# CP_Scheme.net
KiCad netlist of a schematic drawn in Altium Designer
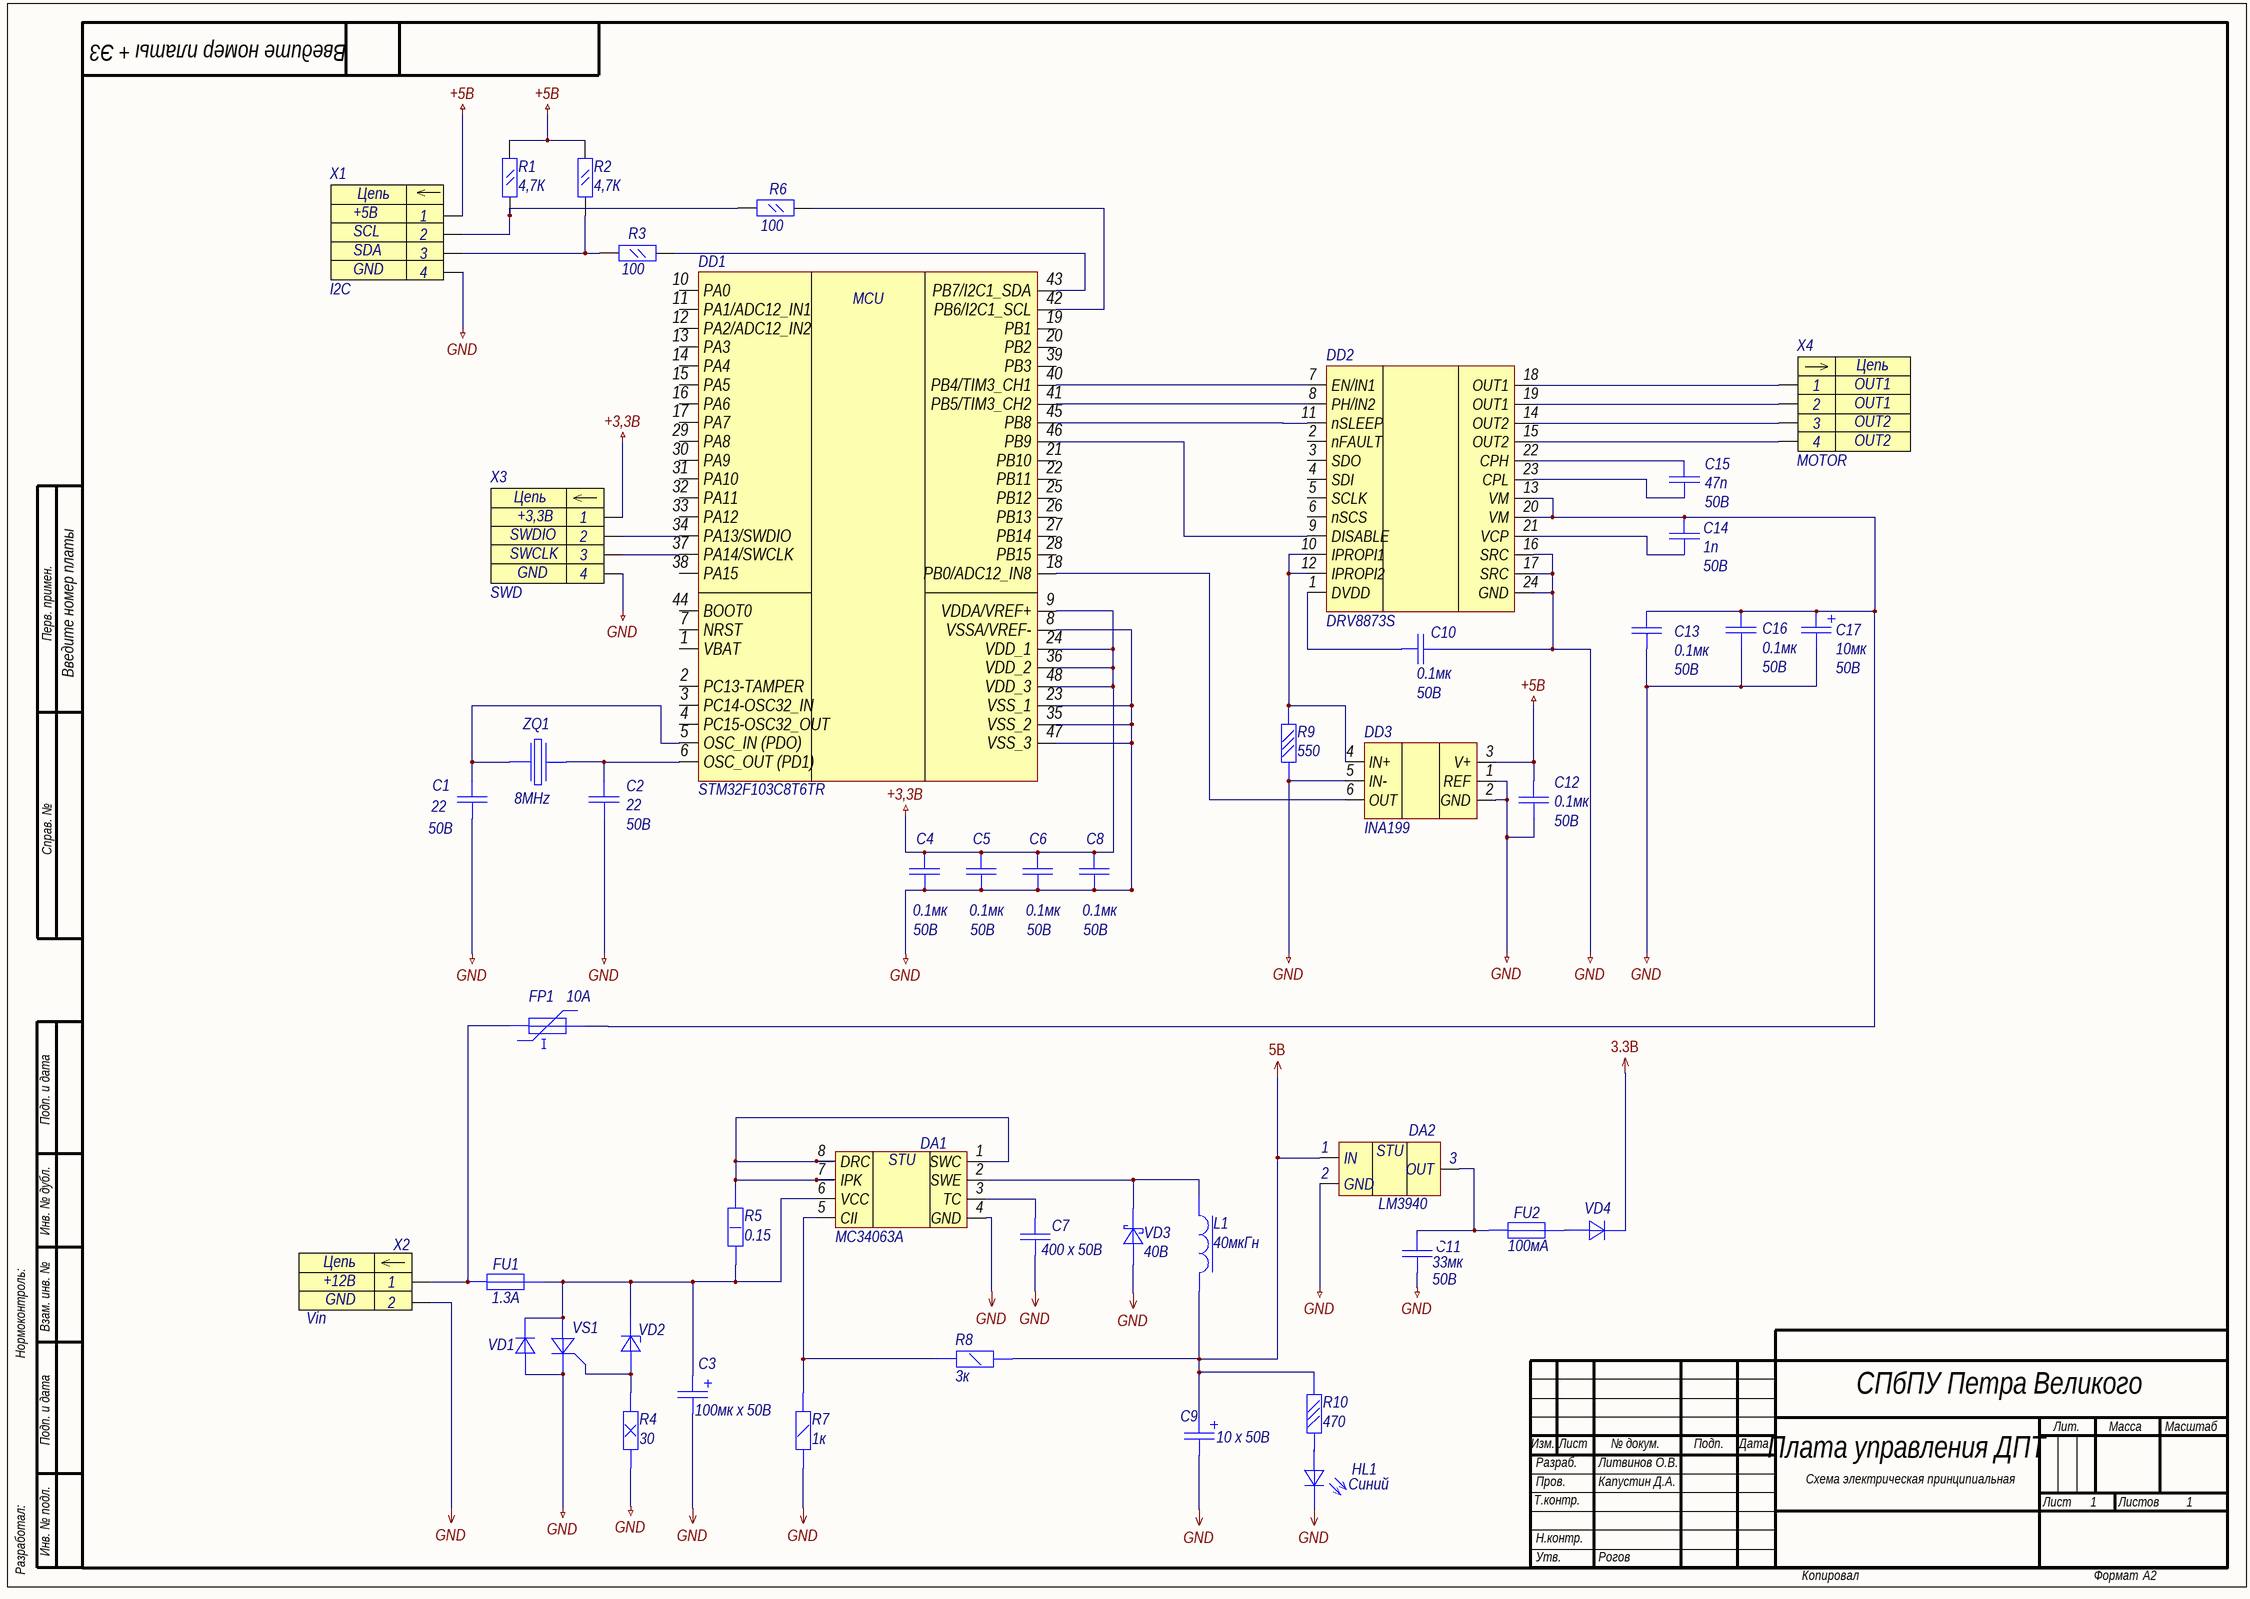
[diagram p0: CP_Scheme.SchDoc]

(export (version "E")
  (design (tool "Eeschema 10.0.6"))
  (components
    (comp (ref "C1")
      (value "22")
      (footprint "C0603")
      (fields (field (name "VOLTAGE") "50В") (field (name "Comment") "Capacitor"))
      (libsource (lib "Capacitor_GOST") (part "Capacitor"))
    )
    (comp (ref "C2")
      (value "22")
      (footprint "C0603")
      (fields (field (name "VOLTAGE") "50В") (field (name "Comment") "Capacitor"))
      (libsource (lib "Capacitor_GOST") (part "Capacitor"))
    )
    (comp (ref "C3")
      (value "Capacitor-E")
      (footprint "C1206")
      (fields (field (name "ЁМКОСТЬ") "100мк х 50В") (field (name "PUBLISHER") "Олег Литвинов"))
      (libsource (lib "Capacitor GOST") (part "Capacitor-E"))
    )
    (comp (ref "C4")
      (value "0.1мк")
      (footprint "C0603")
      (fields (field (name "VOLTAGE") "50В") (field (name "Comment") "Capacitor"))
      (libsource (lib "Capacitor_GOST") (part "Capacitor"))
    )
    (comp (ref "C5")
      (value "0.1мк")
      (footprint "C0603")
      (fields (field (name "VOLTAGE") "50В") (field (name "Comment") "Capacitor"))
      (libsource (lib "Capacitor_GOST") (part "Capacitor"))
    )
    (comp (ref "C6")
      (value "0.1мк")
      (footprint "C0603")
      (fields (field (name "VOLTAGE") "50В") (field (name "Comment") "Capacitor"))
      (libsource (lib "Capacitor_GOST") (part "Capacitor"))
    )
    (comp (ref "C7")
      (value "Capacitor")
      (footprint "R0805")
      (fields (field (name "ЁМКОСТЬ") "400 х 50В") (field (name "PUBLISHER") "Andrew Danich"))
      (libsource (lib "Capacitor GOST") (part "Capacitor"))
    )
    (comp (ref "C8")
      (value "0.1мк")
      (footprint "C0603")
      (fields (field (name "VOLTAGE") "50В") (field (name "Comment") "Capacitor"))
      (libsource (lib "Capacitor_GOST") (part "Capacitor"))
    )
    (comp (ref "C9")
      (value "Capacitor-E")
      (footprint "C1206")
      (fields (field (name "ЁМКОСТЬ") "10 х 50В") (field (name "PUBLISHER") "Олег Литвинов"))
      (libsource (lib "Capacitor GOST") (part "Capacitor-E"))
    )
    (comp (ref "C10")
      (value "0.1мк")
      (footprint "C0603")
      (fields (field (name "VOLTAGE") "50В") (field (name "Comment") "Capacitor"))
      (libsource (lib "Capacitor_GOST") (part "Capacitor"))
    )
    (comp (ref "C11")
      (value "33мк")
      (footprint "C0805")
      (fields (field (name "VOLTAGE") "50В") (field (name "Comment") "Capacitor"))
      (libsource (lib "Capacitor_GOST") (part "Capacitor"))
    )
    (comp (ref "C12")
      (value "0.1мк")
      (footprint "C0603")
      (fields (field (name "VOLTAGE") "50В") (field (name "Comment") "Capacitor"))
      (libsource (lib "Capacitor_GOST") (part "Capacitor"))
    )
    (comp (ref "C13")
      (value "0.1мк")
      (footprint "C0603")
      (fields (field (name "VOLTAGE") "50В") (field (name "Comment") "Capacitor"))
      (libsource (lib "Capacitor_GOST") (part "Capacitor"))
    )
    (comp (ref "C14")
      (value "1п")
      (footprint "C0603")
      (fields (field (name "VOLTAGE") "50В") (field (name "Comment") "Capacitor"))
      (libsource (lib "Capacitor_GOST") (part "Capacitor"))
    )
    (comp (ref "C15")
      (value "47п")
      (footprint "C0603")
      (fields (field (name "VOLTAGE") "50В") (field (name "Comment") "Capacitor"))
      (libsource (lib "Capacitor_GOST") (part "Capacitor"))
    )
    (comp (ref "C16")
      (value "0.1мк")
      (footprint "C0603")
      (fields (field (name "VOLTAGE") "50В") (field (name "Comment") "Capacitor"))
      (libsource (lib "Capacitor_GOST") (part "Capacitor"))
    )
    (comp (ref "C17")
      (value "10мк")
      (footprint "C3216-p")
      (fields (field (name "VOLTAGE") "50В") (field (name "Comment") "Capacitor-T"))
      (libsource (lib "Capacitor_GOST") (part "Capacitor-T"))
    )
    (comp (ref "DA1")
      (value "MC34063A")
      (footprint "PCBComponent_1")
      (libsource (lib "MCP2200_UART_USB") (part "MC34063A"))
    )
    (comp (ref "DA2")
      (value "LM3940")
      (footprint "SOT95P237X112-3N")
      (fields (field (name "ITEM ID") "LM3940"))
      (libsource (lib "MCP2200_UART_USB") (part "LM3940"))
    )
    (comp (ref "DD1")
      (value "STM32F103C8T6TR")
      (footprint "LQFP-48")
      (libsource (lib "Schlib") (part "STM32F103C8T6TR"))
    )
    (comp (ref "DD2") (value "DRV8873S") (footprint "28_Pins") (libsource (lib "Schlib1") (part "DRV8873S")))
    (comp (ref "DD3") (value "INA199") (footprint "SOT23-6_N") (libsource (lib "Schlib1") (part "INA199")))
    (comp (ref "FP1")
      (value "Fuse_PTC")
      (footprint "F1812")
      (fields (field (name "PART NUMBER") "miniSMDC050F-2") (field (name "RATED CURRENT") "10А"))
      (libsource (lib "Lib_IMP_GOST") (part "Fuse_PTC"))
    )
    (comp (ref "FU1")
      (value "1.3A")
      (footprint "F1812")
      (fields (field (name "Comment") "Fuse"))
      (libsource (lib "Fuse_GOST") (part "Fuse"))
    )
    (comp (ref "FU2")
      (value "100мA")
      (footprint "F1812")
      (fields (field (name "Comment") "Fuse"))
      (libsource (lib "Fuse_GOST") (part "Fuse"))
    )
    (comp (ref "HL1")
      (value "LED_3V")
      (footprint "LD0805")
      (fields (field (name "ЦВЕТ") "Синий") (field (name "PUBLISHER") "Andrew Danich"))
      (libsource (lib "Led GOST") (part "Led-1"))
    )
    (comp (ref "L1")
      (value "40мкГн")
      (footprint "МДГ-2")
      (fields
        (field (name "PART NUMBER") "КИВ18-100")
        (field (name "TOLERANCE") "±10%")
        (field (name "MANUFACTURER") "ОАО \"МСТАТОР\"")
        (field (name "PUBLISHER") "Andrew Danich")
      )
      (libsource (lib "Lib_GOST") (part "Coil"))
    )
    (comp (ref "R1")
      (value "Res_0.125")
      (footprint "R0805")
      (fields (field (name "IMPEDANCE") "4,7К"))
      (libsource (lib "GOST_Resistors") (part "Res_0.125"))
    )
    (comp (ref "R2")
      (value "Res_0.125")
      (footprint "R0805")
      (fields (field (name "IMPEDANCE") "4,7К"))
      (libsource (lib "GOST_Resistors") (part "Res_0.125"))
    )
    (comp (ref "R3")
      (value "Res_0.125")
      (footprint "R0805")
      (fields (field (name "IMPEDANCE") "100"))
      (libsource (lib "GOST_Resistors") (part "Res_0.125"))
    )
    (comp (ref "R4")
      (value "Resistor_10,0W")
      (footprint "R0805")
      (fields (field (name "СОПРОТИВЛЕНИЕ") "30"))
      (libsource (lib "Resistor_GOST") (part "Resistor_10,0W"))
    )
    (comp (ref "R5")
      (value "0.15")
      (footprint "R0805")
      (fields (field (name "Comment") "Resistor_1,0W"))
      (libsource (lib "Resistor_GOST") (part "Resistor_1,0W"))
    )
    (comp (ref "R6")
      (value "Res_0.125")
      (footprint "R0805")
      (fields (field (name "IMPEDANCE") "100"))
      (libsource (lib "GOST_Resistors") (part "Res_0.125"))
    )
    (comp (ref "R7")
      (value "1к")
      (footprint "R0805")
      (fields (field (name "Comment") "Resistor_0,25W"))
      (libsource (lib "Resistor_GOST") (part "Resistor_0,25W"))
    )
    (comp (ref "R8")
      (value "3к")
      (footprint "R0805")
      (fields (field (name "Comment") "Resistor_0,25W"))
      (libsource (lib "Resistor_GOST") (part "Resistor_0,25W"))
    )
    (comp (ref "R9")
      (value "550")
      (footprint "R0402")
      (fields (field (name "Comment") "Resistor_0,05W"))
      (libsource (lib "") (part "Resistor_0,05W_1"))
    )
    (comp (ref "R10")
      (value "Resistor_0,05W")
      (footprint "R0805")
      (fields (field (name "СОПРОТИВЛЕНИЕ") "470"))
      (libsource (lib "Resistor_GOST") (part "Resistor_0,05W"))
    )
    (comp (ref "VD1") (value "Diode") (footprint "SOD-123") (libsource (lib "Diode_GOST") (part "Diode")))
    (comp (ref "VD2")
      (value "Suppressor")
      (footprint "DO-214AA")
      (libsource (lib "Diode_GOST") (part "Suppressor"))
    )
    (comp (ref "VD3")
      (value "Schottky")
      (footprint "DO-214AC")
      (description "BYV10-40")
      (fields (field (name "МАКСИМАЛЬНОЕ ОБРАТНОЕ НАПРЯЖЕНИЕ") "40В"))
      (libsource (lib "Diode_GOST") (part "Schottky"))
    )
    (comp (ref "VD4") (value "Diode") (footprint "SOD-123") (libsource (lib "Diode_GOST") (part "Diode")))
    (comp (ref "VS1")
      (value "tiristor")
      (footprint "SOT95P237X112-3N")
      (libsource (lib "Schlib1") (part "tiristor"))
    )
    (comp (ref "X1")
      (value "I2C")
      (footprint "CWF-4")
      (fields
        (field (name "GND") "GND")
        (field (name "CLOCK") "SCL")
        (field (name "DATA") "SDA")
        (field (name "U") "+5В")
        (field (name "CREATE") "DeathSpeaker")
      )
      (libsource (lib "Schlib") (part "I2C_2"))
    )
    (comp (ref "X2")
      (value "Vin")
      (footprint "DJK-02-Series")
      (fields (field (name "U") "+12В") (field (name "GND") "GND") (field (name "CREATE") "DeathSpeaker"))
      (libsource (lib "MCP2200_UART_USB") (part "Vin"))
    )
    (comp (ref "X3") (value "SWD") (footprint "WF-4") (libsource (lib "Schlib") (part "SWD")))
    (comp (ref "X4")
      (value "MOTOR")
      (footprint "90136-1x04")
      (libsource (lib "Schlib1") (part "OUTPUT_MOTOR"))
    )
    (comp (ref "ZQ1")
      (value "Crystal")
      (footprint "SMD 6x3.5mm")
      (fields
        (field (name "PART NUMBER") "РК463-8ВП-8000К")
        (field (name "OUTPUT FREQUENCY") "8MHz")
        (field (name "MANUFACTURER") "ОАО \"ПЬЕЗО\"")
        (field (name "PUBLISHER") "Andrew Danich")
      )
      (libsource (lib "Lib_GOST") (part "Crystal"))
    )
  )
  (nets
    (net (code "1") (name "+3,3В") (class "Default")
      (node (ref "C4") (pin "2") (pinfunction "2_2") (pintype "passive"))
      (node (ref "C5") (pin "2") (pinfunction "2_2") (pintype "passive"))
      (node (ref "C6") (pin "2") (pinfunction "2_2") (pintype "passive"))
      (node (ref "C8") (pin "2") (pinfunction "2_2") (pintype "passive"))
      (node (ref "DD1") (pin "24") (pinfunction "VDD_1_24") (pintype "passive"))
      (node (ref "DD1") (pin "36") (pinfunction "VDD_2_36") (pintype "passive"))
      (node (ref "DD1") (pin "48") (pinfunction "VDD_3_48") (pintype "passive"))
      (node (ref "DD1") (pin "9") (pinfunction "VDDA/VREF+_9") (pintype "passive"))
      (node (ref "X3") (pin "1") (pinfunction "1_1") (pintype "passive"))
    )
    (net (code "2") (name "+5В") (class "Default")
      (node (ref "C12") (pin "2") (pinfunction "2_2") (pintype "passive"))
      (node (ref "DD3") (pin "3") (pinfunction "V+_3") (pintype "passive"))
      (node (ref "R1") (pin "1") (pinfunction "C1-_1") (pintype "power_in"))
      (node (ref "R2") (pin "1") (pinfunction "C1-_1") (pintype "power_in"))
      (node (ref "X1") (pin "1") (pinfunction "1_1") (pintype "passive"))
    )
    (net (code "3") (name "3.3В") (class "Default")
      (node (ref "VD4") (pin "2") (pinfunction "К_2") (pintype "passive"))
    )
    (net (code "4") (name "5В") (class "Default")
      (node (ref "C9") (pin "1") (pinfunction "1_1") (pintype "passive"))
      (node (ref "DA2") (pin "1") (pinfunction "IN_1") (pintype "passive"))
      (node (ref "L1") (pin "2") (pinfunction "2_2") (pintype "passive"))
      (node (ref "R10") (pin "2") (pinfunction "2_2") (pintype "passive"))
      (node (ref "R8") (pin "2") (pinfunction "2_2") (pintype "passive"))
    )
    (net (code "5") (name "GND") (class "Default")
      (node (ref "C1") (pin "2") (pinfunction "2_2") (pintype "passive"))
      (node (ref "C10") (pin "2") (pinfunction "2_2") (pintype "passive"))
      (node (ref "C11") (pin "2") (pinfunction "2_2") (pintype "passive"))
      (node (ref "C12") (pin "1") (pinfunction "1_1") (pintype "passive"))
      (node (ref "C13") (pin "1") (pinfunction "1_1") (pintype "passive"))
      (node (ref "C16") (pin "2") (pinfunction "2_2") (pintype "passive"))
      (node (ref "C17") (pin "2") (pinfunction "2_2") (pintype "passive"))
      (node (ref "C2") (pin "2") (pinfunction "2_2") (pintype "passive"))
      (node (ref "C3") (pin "2") (pinfunction "2_2") (pintype "passive"))
      (node (ref "C4") (pin "1") (pinfunction "1_1") (pintype "passive"))
      (node (ref "C5") (pin "1") (pinfunction "1_1") (pintype "passive"))
      (node (ref "C6") (pin "1") (pinfunction "1_1") (pintype "passive"))
      (node (ref "C7") (pin "1") (pinfunction "1_1") (pintype "passive"))
      (node (ref "C8") (pin "1") (pinfunction "1_1") (pintype "passive"))
      (node (ref "C9") (pin "2") (pinfunction "2_2") (pintype "passive"))
      (node (ref "DA1") (pin "4") (pinfunction "GND_4") (pintype "passive"))
      (node (ref "DA2") (pin "2") (pinfunction "GND_2") (pintype "passive"))
      (node (ref "DD1") (pin "23") (pinfunction "VSS_1_23") (pintype "passive"))
      (node (ref "DD1") (pin "35") (pinfunction "VSS_2_35") (pintype "passive"))
      (node (ref "DD1") (pin "47") (pinfunction "VSS_3_47") (pintype "passive"))
      (node (ref "DD1") (pin "8") (pinfunction "VSSA/VREF-_8") (pintype "passive"))
      (node (ref "DD2") (pin "16") (pinfunction "SRC_16") (pintype "passive"))
      (node (ref "DD2") (pin "17") (pinfunction "SRC_17") (pintype "passive"))
      (node (ref "DD2") (pin "24") (pinfunction "GND_24") (pintype "passive"))
      (node (ref "DD3") (pin "1") (pinfunction "REF_1") (pintype "passive"))
      (node (ref "DD3") (pin "2") (pinfunction "GND_2") (pintype "passive"))
      (node (ref "DD3") (pin "5") (pinfunction "IN-_5") (pintype "passive"))
      (node (ref "HL1") (pin "2") (pinfunction "К_2") (pintype "passive"))
      (node (ref "R4") (pin "1") (pinfunction "1_1") (pintype "passive"))
      (node (ref "R7") (pin "1") (pinfunction "1_1") (pintype "passive"))
      (node (ref "R9") (pin "1") (pinfunction "1_1") (pintype "passive"))
      (node (ref "VD1") (pin "1") (pinfunction "А_1") (pintype "passive"))
      (node (ref "VD3") (pin "1") (pinfunction "А_1") (pintype "passive"))
      (node (ref "VS1") (pin "3") (pinfunction "К_3") (pintype "passive"))
      (node (ref "X1") (pin "4") (pinfunction "4_4") (pintype "passive"))
      (node (ref "X2") (pin "2") (pinfunction "2_2") (pintype "passive"))
      (node (ref "X3") (pin "4") (pinfunction "4_4") (pintype "passive"))
    )
    (net (code "6") (name "Net-(C13-Pad2)") (class "Default")
      (node (ref "C13") (pin "2") (pinfunction "2_2") (pintype "passive"))
      (node (ref "C14") (pin "2") (pinfunction "2_2") (pintype "passive"))
      (node (ref "C16") (pin "1") (pinfunction "1_1") (pintype "passive"))
      (node (ref "C17") (pin "1") (pinfunction "1_1") (pintype "passive"))
      (node (ref "DD2") (pin "13") (pinfunction "VM_13") (pintype "passive"))
      (node (ref "DD2") (pin "20") (pinfunction "VM_20") (pintype "passive"))
      (node (ref "FP1") (pin "2") (pinfunction "2_2") (pintype "passive"))
    )
    (net (code "7") (name "Net-(DA1-CII)") (class "Default")
      (node (ref "DA1") (pin "5") (pinfunction "CII_5") (pintype "passive"))
      (node (ref "R7") (pin "2") (pinfunction "2_2") (pintype "passive"))
      (node (ref "R8") (pin "1") (pinfunction "1_1") (pintype "passive"))
    )
    (net (code "8") (name "Net-(DA1-DRC)") (class "Default")
      (node (ref "DA1") (pin "1") (pinfunction "SWC_1") (pintype "passive"))
      (node (ref "DA1") (pin "7") (pinfunction "IPK_7") (pintype "passive"))
      (node (ref "DA1") (pin "8") (pinfunction "DRC_8") (pintype "passive"))
      (node (ref "R5") (pin "2") (pinfunction "2_2") (pintype "passive"))
    )
    (net (code "9") (name "Net-(DA1-SWE)") (class "Default")
      (node (ref "DA1") (pin "2") (pinfunction "SWE_2") (pintype "passive"))
      (node (ref "L1") (pin "1") (pinfunction "1_1") (pintype "passive"))
      (node (ref "VD3") (pin "2") (pinfunction "К_2") (pintype "passive"))
    )
    (net (code "10") (name "Net-(DA1-TC)") (class "Default")
      (node (ref "C7") (pin "2") (pinfunction "2_2") (pintype "passive"))
      (node (ref "DA1") (pin "3") (pinfunction "TC_3") (pintype "passive"))
    )
    (net (code "11") (name "Net-(DA1-VCC)") (class "Default")
      (node (ref "C3") (pin "1") (pinfunction "1_1") (pintype "passive"))
      (node (ref "DA1") (pin "6") (pinfunction "VCC_6") (pintype "passive"))
      (node (ref "FU1") (pin "2") (pinfunction "2_2") (pintype "passive"))
      (node (ref "R5") (pin "1") (pinfunction "1_1") (pintype "passive"))
      (node (ref "VD1") (pin "2") (pinfunction "К_2") (pintype "passive"))
      (node (ref "VD2") (pin "2") (pinfunction "К_2") (pintype "passive"))
      (node (ref "VS1") (pin "2") (pinfunction "А_2") (pintype "passive"))
    )
    (net (code "12") (name "Net-(DA2-OUT)") (class "Default")
      (node (ref "C11") (pin "1") (pinfunction "1_1") (pintype "passive"))
      (node (ref "DA2") (pin "3") (pinfunction "OUT_3") (pintype "passive"))
      (node (ref "FU2") (pin "1") (pinfunction "1_1") (pintype "passive"))
    )
    (net (code "13") (name "Net-(DD1-OSC_IN_(PDO))") (class "Default")
      (node (ref "C1") (pin "1") (pinfunction "1_1") (pintype "passive"))
      (node (ref "DD1") (pin "5") (pinfunction "OSC_IN_(PDO)_5") (pintype "passive"))
      (node (ref "ZQ1") (pin "1") (pinfunction "1_1") (pintype "passive"))
    )
    (net (code "14") (name "Net-(DD1-OSC_OUT_(PD1))") (class "Default")
      (node (ref "C2") (pin "1") (pinfunction "1_1") (pintype "passive"))
      (node (ref "DD1") (pin "6") (pinfunction "OSC_OUT_(PD1)_6") (pintype "passive"))
      (node (ref "ZQ1") (pin "3") (pinfunction "3_3") (pintype "passive"))
    )
    (net (code "15") (name "Net-(DD1-PA13{slash}SWDIO)") (class "Default")
      (node (ref "DD1") (pin "34") (pinfunction "PA13/SWDIO_34") (pintype "passive"))
      (node (ref "X3") (pin "2") (pinfunction "2_2") (pintype "passive"))
    )
    (net (code "16") (name "Net-(DD1-PA14{slash}SWCLK)") (class "Default")
      (node (ref "DD1") (pin "37") (pinfunction "PA14/SWCLK_37") (pintype "passive"))
      (node (ref "X3") (pin "3") (pinfunction "3_3") (pintype "passive"))
    )
    (net (code "17") (name "Net-(DD1-PB0{slash}ADC12_IN8)") (class "Default")
      (node (ref "DD1") (pin "18") (pinfunction "PB0/ADC12_IN8_18") (pintype "passive"))
      (node (ref "DD3") (pin "6") (pinfunction "OUT_6") (pintype "passive"))
    )
    (net (code "18") (name "Net-(DD1-PB4{slash}TIM3_CH1)") (class "Default")
      (node (ref "DD1") (pin "40") (pinfunction "PB4/TIM3_CH1_40") (pintype "passive"))
      (node (ref "DD2") (pin "7") (pinfunction "EN/IN1_7") (pintype "passive"))
    )
    (net (code "19") (name "Net-(DD1-PB5{slash}TIM3_CH2)") (class "Default")
      (node (ref "DD1") (pin "41") (pinfunction "PB5/TIM3_CH2_41") (pintype "passive"))
      (node (ref "DD2") (pin "8") (pinfunction "PH/IN2_8") (pintype "passive"))
    )
    (net (code "20") (name "Net-(DD1-PB6{slash}I2C1_SCL)") (class "Default")
      (node (ref "DD1") (pin "42") (pinfunction "PB6/I2C1_SCL_42") (pintype "passive"))
      (node (ref "R6") (pin "2") (pinfunction "C1-_2") (pintype "power_in"))
    )
    (net (code "21") (name "Net-(DD1-PB7{slash}I2C1_SDA)") (class "Default")
      (node (ref "DD1") (pin "43") (pinfunction "PB7/I2C1_SDA_43") (pintype "passive"))
      (node (ref "R3") (pin "2") (pinfunction "C1-_2") (pintype "power_in"))
    )
    (net (code "22") (name "Net-(DD1-PB8)") (class "Default")
      (node (ref "DD1") (pin "45") (pinfunction "PB8_45") (pintype "passive"))
      (node (ref "DD2") (pin "11") (pinfunction "nSLEEP_11") (pintype "passive"))
    )
    (net (code "23") (name "Net-(DD1-PB9)") (class "Default")
      (node (ref "DD1") (pin "46") (pinfunction "PB9_46") (pintype "passive"))
      (node (ref "DD2") (pin "9") (pinfunction "DISABLE_9") (pintype "passive"))
    )
    (net (code "24") (name "Net-(DD2-CPH)") (class "Default")
      (node (ref "C15") (pin "2") (pinfunction "2_2") (pintype "passive"))
      (node (ref "DD2") (pin "22") (pinfunction "CPH_22") (pintype "passive"))
    )
    (net (code "25") (name "Net-(DD2-CPL)") (class "Default")
      (node (ref "C15") (pin "1") (pinfunction "1_1") (pintype "passive"))
      (node (ref "DD2") (pin "23") (pinfunction "CPL_23") (pintype "passive"))
    )
    (net (code "26") (name "Net-(DD2-DVDD)") (class "Default")
      (node (ref "C10") (pin "1") (pinfunction "1_1") (pintype "passive"))
      (node (ref "DD2") (pin "1") (pinfunction "DVDD_1") (pintype "passive"))
    )
    (net (code "27") (name "Net-(DD2-IPROPI1)") (class "Default")
      (node (ref "DD2") (pin "10") (pinfunction "IPROPI1_10") (pintype "passive"))
      (node (ref "DD2") (pin "12") (pinfunction "IPROPI2_12") (pintype "passive"))
      (node (ref "DD3") (pin "4") (pinfunction "IN+_4") (pintype "passive"))
      (node (ref "R9") (pin "2") (pinfunction "2_2") (pintype "passive"))
    )
    (net (code "28") (name "Net-(DD2-OUT1-Pad18)") (class "Default")
      (node (ref "DD2") (pin "18") (pinfunction "OUT1_18") (pintype "passive"))
      (node (ref "X4") (pin "1") (pinfunction "1_1") (pintype "passive"))
    )
    (net (code "29") (name "Net-(DD2-OUT1-Pad19)") (class "Default")
      (node (ref "DD2") (pin "19") (pinfunction "OUT1_19") (pintype "passive"))
      (node (ref "X4") (pin "2") (pinfunction "2_2") (pintype "passive"))
    )
    (net (code "30") (name "Net-(DD2-OUT2-Pad14)") (class "Default")
      (node (ref "DD2") (pin "14") (pinfunction "OUT2_14") (pintype "passive"))
      (node (ref "X4") (pin "3") (pinfunction "3_3") (pintype "passive"))
    )
    (net (code "31") (name "Net-(DD2-OUT2-Pad15)") (class "Default")
      (node (ref "DD2") (pin "15") (pinfunction "OUT2_15") (pintype "passive"))
      (node (ref "X4") (pin "4") (pinfunction "4_4") (pintype "passive"))
    )
    (net (code "32") (name "Net-(DD2-VCP)") (class "Default")
      (node (ref "C14") (pin "1") (pinfunction "1_1") (pintype "passive"))
      (node (ref "DD2") (pin "21") (pinfunction "VCP_21") (pintype "passive"))
    )
    (net (code "33") (name "Net-(FP1-Pad1)") (class "Default")
      (node (ref "FP1") (pin "1") (pinfunction "1_1") (pintype "passive"))
      (node (ref "FU1") (pin "1") (pinfunction "1_1") (pintype "passive"))
      (node (ref "X2") (pin "1") (pinfunction "1_1") (pintype "passive"))
    )
    (net (code "34") (name "Net-(HL1-А)") (class "Default")
      (node (ref "HL1") (pin "1") (pinfunction "А_1") (pintype "passive"))
      (node (ref "R10") (pin "1") (pinfunction "1_1") (pintype "passive"))
    )
    (net (code "35") (name "Net-(R1-C1--Pad2)") (class "Default")
      (node (ref "R1") (pin "2") (pinfunction "C1-_2") (pintype "power_in"))
      (node (ref "R6") (pin "1") (pinfunction "C1-_1") (pintype "power_in"))
      (node (ref "X1") (pin "2") (pinfunction "2_2") (pintype "passive"))
    )
    (net (code "36") (name "Net-(R2-C1--Pad2)") (class "Default")
      (node (ref "R2") (pin "2") (pinfunction "C1-_2") (pintype "power_in"))
      (node (ref "R3") (pin "1") (pinfunction "C1-_1") (pintype "power_in"))
      (node (ref "X1") (pin "3") (pinfunction "3_3") (pintype "passive"))
    )
    (net (code "37") (name "Net-(VD2-А)") (class "Default")
      (node (ref "R4") (pin "2") (pinfunction "2_2") (pintype "passive"))
      (node (ref "VD2") (pin "1") (pinfunction "А_1") (pintype "passive"))
      (node (ref "VS1") (pin "1") (pinfunction "G_1") (pintype "passive"))
    )
    (net (code "38") (name "Net-(VD4-А)") (class "Default")
      (node (ref "FU2") (pin "2") (pinfunction "2_2") (pintype "passive"))
      (node (ref "VD4") (pin "1") (pinfunction "А_1") (pintype "passive"))
    )
    (net (code "39") (name "unconnected-(DD1-BOOT0-Pad44)") (class "Default")
      (node (ref "DD1") (pin "44") (pinfunction "BOOT0_44") (pintype "passive"))
    )
    (net (code "40") (name "unconnected-(DD1-NRST-Pad7)") (class "Default")
      (node (ref "DD1") (pin "7") (pinfunction "NRST_7") (pintype "passive"))
    )
    (net (code "41") (name "unconnected-(DD1-PA0-Pad10)") (class "Default")
      (node (ref "DD1") (pin "10") (pinfunction "PA0_10") (pintype "passive"))
    )
    (net (code "42") (name "unconnected-(DD1-PA1{slash}ADC12_IN1-Pad11)") (class "Default")
      (node (ref "DD1") (pin "11") (pinfunction "PA1/ADC12_IN1_11") (pintype "passive"))
    )
    (net (code "43") (name "unconnected-(DD1-PA2{slash}ADC12_IN2-Pad12)") (class "Default")
      (node (ref "DD1") (pin "12") (pinfunction "PA2/ADC12_IN2_12") (pintype "passive"))
    )
    (net (code "44") (name "unconnected-(DD1-PA3-Pad13)") (class "Default")
      (node (ref "DD1") (pin "13") (pinfunction "PA3_13") (pintype "passive"))
    )
    (net (code "45") (name "unconnected-(DD1-PA4-Pad14)") (class "Default")
      (node (ref "DD1") (pin "14") (pinfunction "PA4_14") (pintype "passive"))
    )
    (net (code "46") (name "unconnected-(DD1-PA5-Pad15)") (class "Default")
      (node (ref "DD1") (pin "15") (pinfunction "PA5_15") (pintype "passive"))
    )
    (net (code "47") (name "unconnected-(DD1-PA6-Pad16)") (class "Default")
      (node (ref "DD1") (pin "16") (pinfunction "PA6_16") (pintype "passive"))
    )
    (net (code "48") (name "unconnected-(DD1-PA7-Pad17)") (class "Default")
      (node (ref "DD1") (pin "17") (pinfunction "PA7_17") (pintype "passive"))
    )
    (net (code "49") (name "unconnected-(DD1-PA8-Pad29)") (class "Default")
      (node (ref "DD1") (pin "29") (pinfunction "PA8_29") (pintype "passive"))
    )
    (net (code "50") (name "unconnected-(DD1-PA9-Pad30)") (class "Default")
      (node (ref "DD1") (pin "30") (pinfunction "PA9_30") (pintype "passive"))
    )
    (net (code "51") (name "unconnected-(DD1-PA10-Pad31)") (class "Default")
      (node (ref "DD1") (pin "31") (pinfunction "PA10_31") (pintype "passive"))
    )
    (net (code "52") (name "unconnected-(DD1-PA11-Pad32)") (class "Default")
      (node (ref "DD1") (pin "32") (pinfunction "PA11_32") (pintype "passive"))
    )
    (net (code "53") (name "unconnected-(DD1-PA12-Pad33)") (class "Default")
      (node (ref "DD1") (pin "33") (pinfunction "PA12_33") (pintype "passive"))
    )
    (net (code "54") (name "unconnected-(DD1-PA15-Pad38)") (class "Default")
      (node (ref "DD1") (pin "38") (pinfunction "PA15_38") (pintype "passive"))
    )
    (net (code "55") (name "unconnected-(DD1-PB1-Pad19)") (class "Default")
      (node (ref "DD1") (pin "19") (pinfunction "PB1_19") (pintype "passive"))
    )
    (net (code "56") (name "unconnected-(DD1-PB2-Pad20)") (class "Default")
      (node (ref "DD1") (pin "20") (pinfunction "PB2_20") (pintype "passive"))
    )
    (net (code "57") (name "unconnected-(DD1-PB3-Pad39)") (class "Default")
      (node (ref "DD1") (pin "39") (pinfunction "PB3_39") (pintype "passive"))
    )
    (net (code "58") (name "unconnected-(DD1-PB10-Pad21)") (class "Default")
      (node (ref "DD1") (pin "21") (pinfunction "PB10_21") (pintype "passive"))
    )
    (net (code "59") (name "unconnected-(DD1-PB11-Pad22)") (class "Default")
      (node (ref "DD1") (pin "22") (pinfunction "PB11_22") (pintype "passive"))
    )
    (net (code "60") (name "unconnected-(DD1-PB12-Pad25)") (class "Default")
      (node (ref "DD1") (pin "25") (pinfunction "PB12_25") (pintype "passive"))
    )
    (net (code "61") (name "unconnected-(DD1-PB13-Pad26)") (class "Default")
      (node (ref "DD1") (pin "26") (pinfunction "PB13_26") (pintype "passive"))
    )
    (net (code "62") (name "unconnected-(DD1-PB14-Pad27)") (class "Default")
      (node (ref "DD1") (pin "27") (pinfunction "PB14_27") (pintype "passive"))
    )
    (net (code "63") (name "unconnected-(DD1-PB15-Pad28)") (class "Default")
      (node (ref "DD1") (pin "28") (pinfunction "PB15_28") (pintype "passive"))
    )
    (net (code "64") (name "unconnected-(DD1-PC13-TAMPER-Pad2)") (class "Default")
      (node (ref "DD1") (pin "2") (pinfunction "PC13-TAMPER_2") (pintype "passive"))
    )
    (net (code "65") (name "unconnected-(DD1-PC14-OSC32_IN-Pad3)") (class "Default")
      (node (ref "DD1") (pin "3") (pinfunction "PC14-OSC32_IN_3") (pintype "passive"))
    )
    (net (code "66") (name "unconnected-(DD1-PC15-OSC32_OUT-Pad4)") (class "Default")
      (node (ref "DD1") (pin "4") (pinfunction "PC15-OSC32_OUT_4") (pintype "passive"))
    )
    (net (code "67") (name "unconnected-(DD1-VBAT-Pad1)") (class "Default")
      (node (ref "DD1") (pin "1") (pinfunction "VBAT_1") (pintype "passive"))
    )
    (net (code "68") (name "unconnected-(DD2-SCLK-Pad5)") (class "Default")
      (node (ref "DD2") (pin "5") (pinfunction "SCLK_5") (pintype "passive"))
    )
    (net (code "69") (name "unconnected-(DD2-SDI-Pad4)") (class "Default")
      (node (ref "DD2") (pin "4") (pinfunction "SDI_4") (pintype "passive"))
    )
    (net (code "70") (name "unconnected-(DD2-SDO-Pad3)") (class "Default")
      (node (ref "DD2") (pin "3") (pinfunction "SDO_3") (pintype "passive"))
    )
    (net (code "71") (name "unconnected-(DD2-nFAULT-Pad2)") (class "Default")
      (node (ref "DD2") (pin "2") (pinfunction "nFAULT_2") (pintype "passive"))
    )
    (net (code "72") (name "unconnected-(DD2-nSCS-Pad6)") (class "Default")
      (node (ref "DD2") (pin "6") (pinfunction "nSCS_6") (pintype "passive"))
    )
  )
)
